# Sheet1.net
KiCad netlist of a schematic drawn in Altium Designer
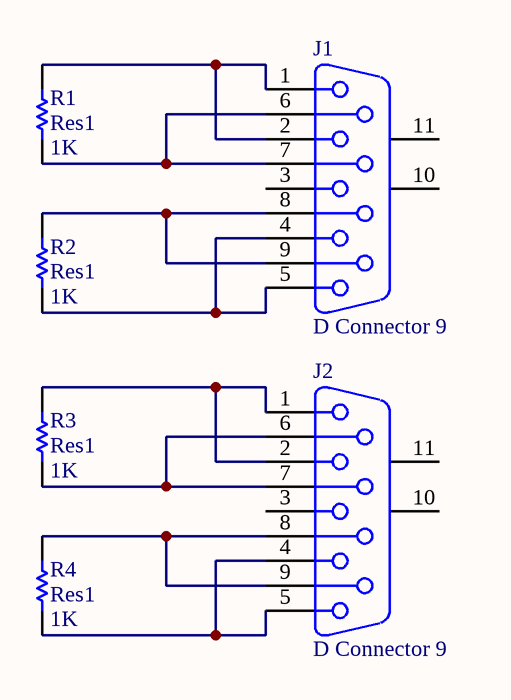
[diagram p0: Sheet1.SchDoc]

(export (version "E")
  (design (tool "Eeschema 10.0.6"))
  (components
    (comp (ref "J1")
      (value "D Connector 9")
      (footprint "DSUB1.385-2H9")
      (description "Receptacle Assembly, 9 Position, Right Angle")
      (fields (field (name "PUBLISHER") "Altium Limited"))
      (libsource (lib "Miscellaneous Connectors") (part "D Connector 9"))
    )
    (comp (ref "J2")
      (value "D Connector 9")
      (footprint "DSUB1.385-2H9")
      (description "Receptacle Assembly, 9 Position, Right Angle")
      (fields (field (name "PUBLISHER") "Altium Limited"))
      (libsource (lib "Miscellaneous Connectors") (part "D Connector 9"))
    )
    (comp (ref "R1")
      (value "Res1")
      (footprint "AXIAL-0.3")
      (description "Resistor")
      (fields (field (name "ALTIUM_VALUE") "1K") (field (name "PUBLISHER") "Altium Limited"))
      (libsource (lib "Miscellaneous Devices") (part "Res1"))
    )
    (comp (ref "R2")
      (value "Res1")
      (footprint "AXIAL-0.3")
      (description "Resistor")
      (fields (field (name "ALTIUM_VALUE") "1K") (field (name "PUBLISHER") "Altium Limited"))
      (libsource (lib "Miscellaneous Devices") (part "Res1"))
    )
    (comp (ref "R3")
      (value "Res1")
      (footprint "AXIAL-0.3")
      (description "Resistor")
      (fields (field (name "ALTIUM_VALUE") "1K") (field (name "PUBLISHER") "Altium Limited"))
      (libsource (lib "Miscellaneous Devices") (part "Res1"))
    )
    (comp (ref "R4")
      (value "Res1")
      (footprint "AXIAL-0.3")
      (description "Resistor")
      (fields (field (name "ALTIUM_VALUE") "1K") (field (name "PUBLISHER") "Altium Limited"))
      (libsource (lib "Miscellaneous Devices") (part "Res1"))
    )
  )
  (nets
    (net (code "1") (name "Net-(J1-Pad1)") (class "Default")
      (node (ref "J1") (pin "1") (pinfunction "1_1") (pintype "passive"))
      (node (ref "J1") (pin "2") (pinfunction "2_2") (pintype "passive"))
      (node (ref "R1") (pin "2") (pinfunction "2_2") (pintype "passive"))
    )
    (net (code "2") (name "Net-(J1-Pad4)") (class "Default")
      (node (ref "J1") (pin "4") (pinfunction "4_4") (pintype "passive"))
      (node (ref "J1") (pin "5") (pinfunction "5_5") (pintype "passive"))
      (node (ref "R2") (pin "1") (pinfunction "1_1") (pintype "passive"))
    )
    (net (code "3") (name "Net-(J1-Pad6)") (class "Default")
      (node (ref "J1") (pin "6") (pinfunction "6_6") (pintype "passive"))
      (node (ref "J1") (pin "7") (pinfunction "7_7") (pintype "passive"))
      (node (ref "R1") (pin "1") (pinfunction "1_1") (pintype "passive"))
    )
    (net (code "4") (name "Net-(J1-Pad8)") (class "Default")
      (node (ref "J1") (pin "8") (pinfunction "8_8") (pintype "passive"))
      (node (ref "J1") (pin "9") (pinfunction "9_9") (pintype "passive"))
      (node (ref "R2") (pin "2") (pinfunction "2_2") (pintype "passive"))
    )
    (net (code "5") (name "Net-(J2-Pad1)") (class "Default")
      (node (ref "J2") (pin "1") (pinfunction "1_1") (pintype "passive"))
      (node (ref "J2") (pin "2") (pinfunction "2_2") (pintype "passive"))
      (node (ref "R3") (pin "2") (pinfunction "2_2") (pintype "passive"))
    )
    (net (code "6") (name "Net-(J2-Pad4)") (class "Default")
      (node (ref "J2") (pin "4") (pinfunction "4_4") (pintype "passive"))
      (node (ref "J2") (pin "5") (pinfunction "5_5") (pintype "passive"))
      (node (ref "R4") (pin "1") (pinfunction "1_1") (pintype "passive"))
    )
    (net (code "7") (name "Net-(J2-Pad6)") (class "Default")
      (node (ref "J2") (pin "6") (pinfunction "6_6") (pintype "passive"))
      (node (ref "J2") (pin "7") (pinfunction "7_7") (pintype "passive"))
      (node (ref "R3") (pin "1") (pinfunction "1_1") (pintype "passive"))
    )
    (net (code "8") (name "Net-(J2-Pad8)") (class "Default")
      (node (ref "J2") (pin "8") (pinfunction "8_8") (pintype "passive"))
      (node (ref "J2") (pin "9") (pinfunction "9_9") (pintype "passive"))
      (node (ref "R4") (pin "2") (pinfunction "2_2") (pintype "passive"))
    )
    (net (code "9") (name "unconnected-(J1-MH1-Pad10)") (class "Default")
      (node (ref "J1") (pin "10") (pinfunction "MH1_10") (pintype "passive"))
    )
    (net (code "10") (name "unconnected-(J1-MH2-Pad11)") (class "Default")
      (node (ref "J1") (pin "11") (pinfunction "MH2_11") (pintype "passive"))
    )
    (net (code "11") (name "unconnected-(J1-Pad3)") (class "Default")
      (node (ref "J1") (pin "3") (pinfunction "3_3") (pintype "passive"))
    )
    (net (code "12") (name "unconnected-(J2-MH1-Pad10)") (class "Default")
      (node (ref "J2") (pin "10") (pinfunction "MH1_10") (pintype "passive"))
    )
    (net (code "13") (name "unconnected-(J2-MH2-Pad11)") (class "Default")
      (node (ref "J2") (pin "11") (pinfunction "MH2_11") (pintype "passive"))
    )
    (net (code "14") (name "unconnected-(J2-Pad3)") (class "Default")
      (node (ref "J2") (pin "3") (pinfunction "3_3") (pintype "passive"))
    )
  )
)
